# RaspberryPiSocket.net
KiCad netlist of a schematic drawn in EAGLE
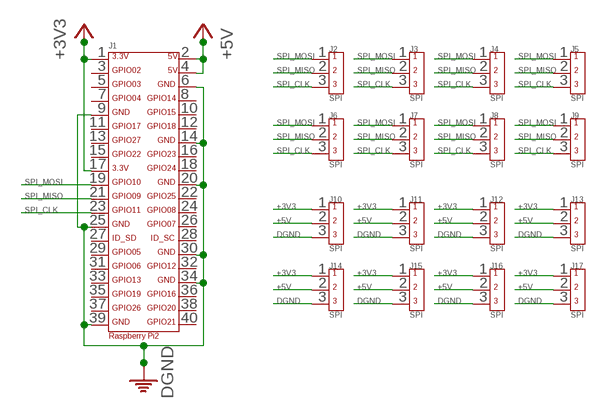
[diagram p0: schematic, sheet 1]

(export (version "E")
  (design (tool "Eeschema 10.0.6"))
  (components
    (comp (ref "J1")
      (value "RPI2")
      (footprint "eagle-import:RPI2")
      (libsource (lib "eagle-import") (part "RPI2"))
    )
    (comp (ref "J2")
      (value "SPI")
      (footprint "eagle-import:CON_HEADER_3_100")
      (libsource (lib "eagle-import") (part "CON_HEADER_3PIN_100"))
    )
    (comp (ref "J3")
      (value "SPI")
      (footprint "eagle-import:CON_HEADER_3_100")
      (libsource (lib "eagle-import") (part "CON_HEADER_3PIN_100"))
    )
    (comp (ref "J4")
      (value "SPI")
      (footprint "eagle-import:CON_HEADER_3_100")
      (libsource (lib "eagle-import") (part "CON_HEADER_3PIN_100"))
    )
    (comp (ref "J5")
      (value "SPI")
      (footprint "eagle-import:CON_HEADER_3_100")
      (libsource (lib "eagle-import") (part "CON_HEADER_3PIN_100"))
    )
    (comp (ref "J6")
      (value "SPI")
      (footprint "eagle-import:CON_HEADER_3_100")
      (libsource (lib "eagle-import") (part "CON_HEADER_3PIN_100"))
    )
    (comp (ref "J7")
      (value "SPI")
      (footprint "eagle-import:CON_HEADER_3_100")
      (libsource (lib "eagle-import") (part "CON_HEADER_3PIN_100"))
    )
    (comp (ref "J8")
      (value "SPI")
      (footprint "eagle-import:CON_HEADER_3_100")
      (libsource (lib "eagle-import") (part "CON_HEADER_3PIN_100"))
    )
    (comp (ref "J9")
      (value "SPI")
      (footprint "eagle-import:CON_HEADER_3_100")
      (libsource (lib "eagle-import") (part "CON_HEADER_3PIN_100"))
    )
    (comp (ref "J10")
      (value "SPI")
      (footprint "eagle-import:CON_HEADER_3_100")
      (libsource (lib "eagle-import") (part "CON_HEADER_3PIN_100"))
    )
    (comp (ref "J11")
      (value "SPI")
      (footprint "eagle-import:CON_HEADER_3_100")
      (libsource (lib "eagle-import") (part "CON_HEADER_3PIN_100"))
    )
    (comp (ref "J12")
      (value "SPI")
      (footprint "eagle-import:CON_HEADER_3_100")
      (libsource (lib "eagle-import") (part "CON_HEADER_3PIN_100"))
    )
    (comp (ref "J13")
      (value "SPI")
      (footprint "eagle-import:CON_HEADER_3_100")
      (libsource (lib "eagle-import") (part "CON_HEADER_3PIN_100"))
    )
    (comp (ref "J14")
      (value "SPI")
      (footprint "eagle-import:CON_HEADER_3_100")
      (libsource (lib "eagle-import") (part "CON_HEADER_3PIN_100"))
    )
    (comp (ref "J15")
      (value "SPI")
      (footprint "eagle-import:CON_HEADER_3_100")
      (libsource (lib "eagle-import") (part "CON_HEADER_3PIN_100"))
    )
    (comp (ref "J16")
      (value "SPI")
      (footprint "eagle-import:CON_HEADER_3_100")
      (libsource (lib "eagle-import") (part "CON_HEADER_3PIN_100"))
    )
    (comp (ref "J17")
      (value "SPI")
      (footprint "eagle-import:CON_HEADER_3_100")
      (libsource (lib "eagle-import") (part "CON_HEADER_3PIN_100"))
    )
  )
  (nets
    (net (code "1") (name "+3V3") (class "Default")
      (node (ref "J1") (pin "1") (pinfunction "1_1") (pintype "passive"))
      (node (ref "J1") (pin "17") (pinfunction "17_17") (pintype "passive"))
      (node (ref "J10") (pin "1") (pinfunction "1_1") (pintype "passive"))
      (node (ref "J11") (pin "1") (pinfunction "1_1") (pintype "passive"))
      (node (ref "J12") (pin "1") (pinfunction "1_1") (pintype "passive"))
      (node (ref "J13") (pin "1") (pinfunction "1_1") (pintype "passive"))
      (node (ref "J14") (pin "1") (pinfunction "1_1") (pintype "passive"))
      (node (ref "J15") (pin "1") (pinfunction "1_1") (pintype "passive"))
      (node (ref "J16") (pin "1") (pinfunction "1_1") (pintype "passive"))
      (node (ref "J17") (pin "1") (pinfunction "1_1") (pintype "passive"))
    )
    (net (code "2") (name "+5V") (class "Default")
      (node (ref "J1") (pin "2") (pinfunction "2_2") (pintype "passive"))
      (node (ref "J1") (pin "4") (pinfunction "4_4") (pintype "passive"))
      (node (ref "J10") (pin "2") (pinfunction "2_2") (pintype "passive"))
      (node (ref "J11") (pin "2") (pinfunction "2_2") (pintype "passive"))
      (node (ref "J12") (pin "2") (pinfunction "2_2") (pintype "passive"))
      (node (ref "J13") (pin "2") (pinfunction "2_2") (pintype "passive"))
      (node (ref "J14") (pin "2") (pinfunction "2_2") (pintype "passive"))
      (node (ref "J15") (pin "2") (pinfunction "2_2") (pintype "passive"))
      (node (ref "J16") (pin "2") (pinfunction "2_2") (pintype "passive"))
      (node (ref "J17") (pin "2") (pinfunction "2_2") (pintype "passive"))
    )
    (net (code "3") (name "/SPI_CLK") (class "Default")
      (node (ref "J1") (pin "23") (pinfunction "23_23") (pintype "passive"))
      (node (ref "J2") (pin "3") (pinfunction "3_3") (pintype "passive"))
      (node (ref "J3") (pin "3") (pinfunction "3_3") (pintype "passive"))
      (node (ref "J4") (pin "3") (pinfunction "3_3") (pintype "passive"))
      (node (ref "J5") (pin "3") (pinfunction "3_3") (pintype "passive"))
      (node (ref "J6") (pin "3") (pinfunction "3_3") (pintype "passive"))
      (node (ref "J7") (pin "3") (pinfunction "3_3") (pintype "passive"))
      (node (ref "J8") (pin "3") (pinfunction "3_3") (pintype "passive"))
      (node (ref "J9") (pin "3") (pinfunction "3_3") (pintype "passive"))
    )
    (net (code "4") (name "/SPI_MISO") (class "Default")
      (node (ref "J1") (pin "21") (pinfunction "21_21") (pintype "passive"))
      (node (ref "J2") (pin "2") (pinfunction "2_2") (pintype "passive"))
      (node (ref "J3") (pin "2") (pinfunction "2_2") (pintype "passive"))
      (node (ref "J4") (pin "2") (pinfunction "2_2") (pintype "passive"))
      (node (ref "J5") (pin "2") (pinfunction "2_2") (pintype "passive"))
      (node (ref "J6") (pin "2") (pinfunction "2_2") (pintype "passive"))
      (node (ref "J7") (pin "2") (pinfunction "2_2") (pintype "passive"))
      (node (ref "J8") (pin "2") (pinfunction "2_2") (pintype "passive"))
      (node (ref "J9") (pin "2") (pinfunction "2_2") (pintype "passive"))
    )
    (net (code "5") (name "/SPI_MOSI") (class "Default")
      (node (ref "J1") (pin "19") (pinfunction "19_19") (pintype "passive"))
      (node (ref "J2") (pin "1") (pinfunction "1_1") (pintype "passive"))
      (node (ref "J3") (pin "1") (pinfunction "1_1") (pintype "passive"))
      (node (ref "J4") (pin "1") (pinfunction "1_1") (pintype "passive"))
      (node (ref "J5") (pin "1") (pinfunction "1_1") (pintype "passive"))
      (node (ref "J6") (pin "1") (pinfunction "1_1") (pintype "passive"))
      (node (ref "J7") (pin "1") (pinfunction "1_1") (pintype "passive"))
      (node (ref "J8") (pin "1") (pinfunction "1_1") (pintype "passive"))
      (node (ref "J9") (pin "1") (pinfunction "1_1") (pintype "passive"))
    )
    (net (code "6") (name "DGND") (class "Default")
      (node (ref "J1") (pin "14") (pinfunction "14_14") (pintype "passive"))
      (node (ref "J1") (pin "20") (pinfunction "20_20") (pintype "passive"))
      (node (ref "J1") (pin "25") (pinfunction "25_25") (pintype "passive"))
      (node (ref "J1") (pin "30") (pinfunction "30_30") (pintype "passive"))
      (node (ref "J1") (pin "34") (pinfunction "34_34") (pintype "passive"))
      (node (ref "J1") (pin "39") (pinfunction "39_39") (pintype "passive"))
      (node (ref "J1") (pin "6") (pinfunction "6_6") (pintype "passive"))
      (node (ref "J1") (pin "9") (pinfunction "9_9") (pintype "passive"))
      (node (ref "J10") (pin "3") (pinfunction "3_3") (pintype "passive"))
      (node (ref "J11") (pin "3") (pinfunction "3_3") (pintype "passive"))
      (node (ref "J12") (pin "3") (pinfunction "3_3") (pintype "passive"))
      (node (ref "J13") (pin "3") (pinfunction "3_3") (pintype "passive"))
      (node (ref "J14") (pin "3") (pinfunction "3_3") (pintype "passive"))
      (node (ref "J15") (pin "3") (pinfunction "3_3") (pintype "passive"))
      (node (ref "J16") (pin "3") (pinfunction "3_3") (pintype "passive"))
      (node (ref "J17") (pin "3") (pinfunction "3_3") (pintype "passive"))
    )
    (net (code "7") (name "unconnected-(J1-Pad3)") (class "Default")
      (node (ref "J1") (pin "3") (pinfunction "3_3") (pintype "passive"))
    )
    (net (code "8") (name "unconnected-(J1-Pad5)") (class "Default")
      (node (ref "J1") (pin "5") (pinfunction "5_5") (pintype "passive"))
    )
    (net (code "9") (name "unconnected-(J1-Pad7)") (class "Default")
      (node (ref "J1") (pin "7") (pinfunction "7_7") (pintype "passive"))
    )
    (net (code "10") (name "unconnected-(J1-Pad8)") (class "Default")
      (node (ref "J1") (pin "8") (pinfunction "8_8") (pintype "passive"))
    )
    (net (code "11") (name "unconnected-(J1-Pad10)") (class "Default")
      (node (ref "J1") (pin "10") (pinfunction "10_10") (pintype "passive"))
    )
    (net (code "12") (name "unconnected-(J1-Pad11)") (class "Default")
      (node (ref "J1") (pin "11") (pinfunction "11_11") (pintype "passive"))
    )
    (net (code "13") (name "unconnected-(J1-Pad12)") (class "Default")
      (node (ref "J1") (pin "12") (pinfunction "12_12") (pintype "passive"))
    )
    (net (code "14") (name "unconnected-(J1-Pad13)") (class "Default")
      (node (ref "J1") (pin "13") (pinfunction "13_13") (pintype "passive"))
    )
    (net (code "15") (name "unconnected-(J1-Pad15)") (class "Default")
      (node (ref "J1") (pin "15") (pinfunction "15_15") (pintype "passive"))
    )
    (net (code "16") (name "unconnected-(J1-Pad16)") (class "Default")
      (node (ref "J1") (pin "16") (pinfunction "16_16") (pintype "passive"))
    )
    (net (code "17") (name "unconnected-(J1-Pad18)") (class "Default")
      (node (ref "J1") (pin "18") (pinfunction "18_18") (pintype "passive"))
    )
    (net (code "18") (name "unconnected-(J1-Pad22)") (class "Default")
      (node (ref "J1") (pin "22") (pinfunction "22_22") (pintype "passive"))
    )
    (net (code "19") (name "unconnected-(J1-Pad24)") (class "Default")
      (node (ref "J1") (pin "24") (pinfunction "24_24") (pintype "passive"))
    )
    (net (code "20") (name "unconnected-(J1-Pad26)") (class "Default")
      (node (ref "J1") (pin "26") (pinfunction "26_26") (pintype "passive"))
    )
    (net (code "21") (name "unconnected-(J1-Pad27)") (class "Default")
      (node (ref "J1") (pin "27") (pinfunction "27_27") (pintype "passive"))
    )
    (net (code "22") (name "unconnected-(J1-Pad28)") (class "Default")
      (node (ref "J1") (pin "28") (pinfunction "28_28") (pintype "passive"))
    )
    (net (code "23") (name "unconnected-(J1-Pad29)") (class "Default")
      (node (ref "J1") (pin "29") (pinfunction "29_29") (pintype "passive"))
    )
    (net (code "24") (name "unconnected-(J1-Pad31)") (class "Default")
      (node (ref "J1") (pin "31") (pinfunction "31_31") (pintype "passive"))
    )
    (net (code "25") (name "unconnected-(J1-Pad32)") (class "Default")
      (node (ref "J1") (pin "32") (pinfunction "32_32") (pintype "passive"))
    )
    (net (code "26") (name "unconnected-(J1-Pad33)") (class "Default")
      (node (ref "J1") (pin "33") (pinfunction "33_33") (pintype "passive"))
    )
    (net (code "27") (name "unconnected-(J1-Pad35)") (class "Default")
      (node (ref "J1") (pin "35") (pinfunction "35_35") (pintype "passive"))
    )
    (net (code "28") (name "unconnected-(J1-Pad36)") (class "Default")
      (node (ref "J1") (pin "36") (pinfunction "36_36") (pintype "passive"))
    )
    (net (code "29") (name "unconnected-(J1-Pad37)") (class "Default")
      (node (ref "J1") (pin "37") (pinfunction "37_37") (pintype "passive"))
    )
    (net (code "30") (name "unconnected-(J1-Pad38)") (class "Default")
      (node (ref "J1") (pin "38") (pinfunction "38_38") (pintype "passive"))
    )
    (net (code "31") (name "unconnected-(J1-Pad40)") (class "Default")
      (node (ref "J1") (pin "40") (pinfunction "40_40") (pintype "passive"))
    )
  )
)
